# Esquematico.net
KiCad netlist of a schematic drawn in EAGLE
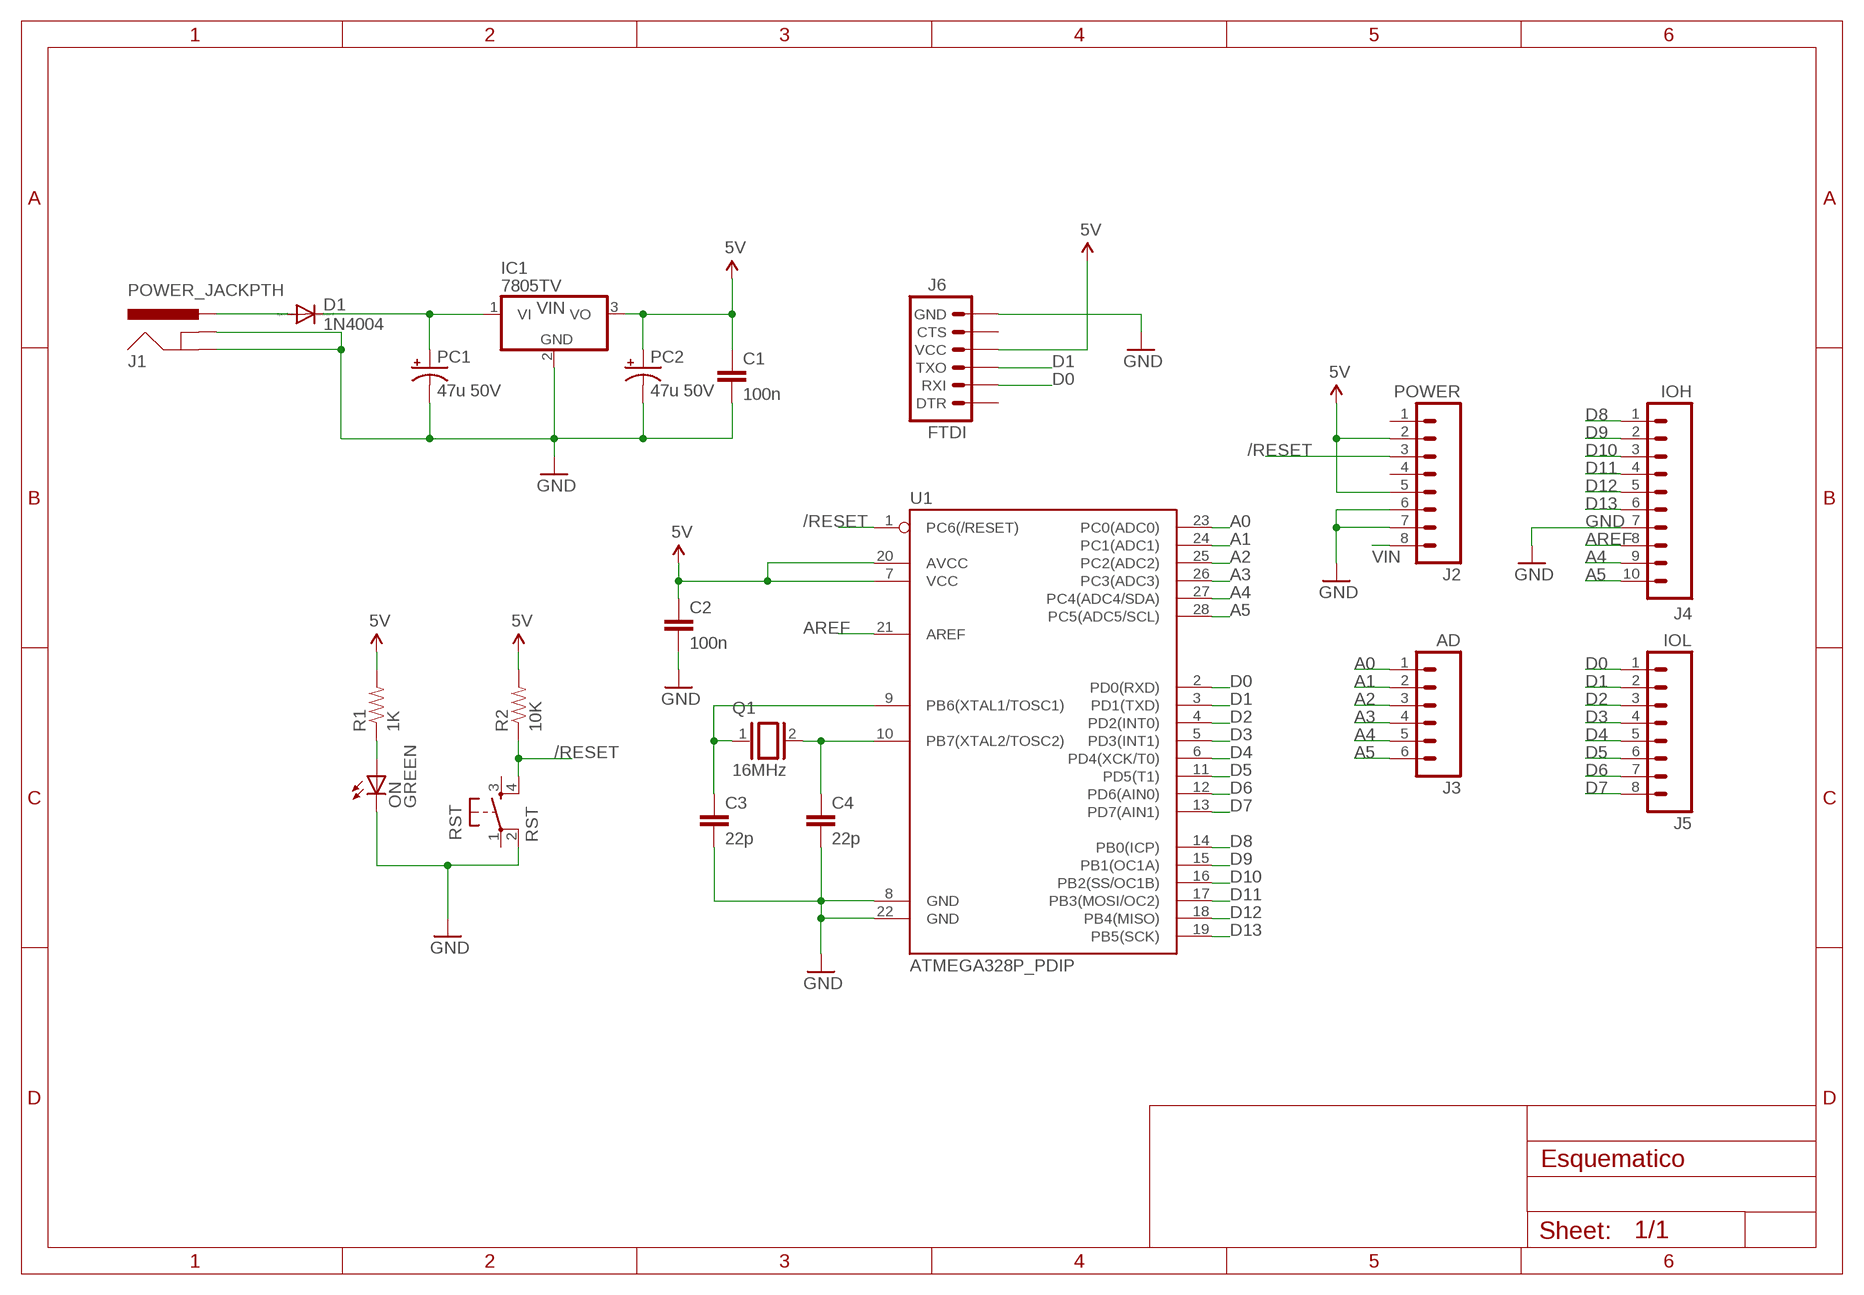
[diagram p0: schematic, sheet 1]

(export (version "E")
  (design (tool "Eeschema 10.0.6"))
  (components
    (comp (ref "C1")
      (value "100n")
      (footprint "eagle-import:C2.5-3")
      (libsource (lib "eagle-import") (part "C2,5-3"))
    )
    (comp (ref "C2")
      (value "100n")
      (footprint "eagle-import:CAP-PTH-SMALLEZ")
      (libsource (lib "eagle-import") (part "CAPEZ"))
    )
    (comp (ref "C3")
      (value "22p")
      (footprint "eagle-import:CAP-PTH-SMALLEZ")
      (libsource (lib "eagle-import") (part "CAPEZ"))
    )
    (comp (ref "C4")
      (value "22p")
      (footprint "eagle-import:CAP-PTH-SMALLEZ")
      (libsource (lib "eagle-import") (part "CAPEZ"))
    )
    (comp (ref "D1")
      (value "1N4004")
      (footprint "eagle-import:DO41-10")
      (libsource (lib "eagle-import") (part "1N4004"))
    )
    (comp (ref "IC1")
      (value "7805TV")
      (footprint "eagle-import:TO220V")
      (libsource (lib "eagle-import") (part "78TV05"))
    )
    (comp (ref "J1")
      (value "POWER_JACKPTH")
      (footprint "eagle-import:POWER_JACK_PTH")
      (libsource (lib "eagle-import") (part "POWER_JACKPTH"))
    )
    (comp (ref "J2")
      (value "POWER")
      (footprint "eagle-import:1X08_PIN1_NO_SILK")
      (libsource (lib "eagle-import") (part "M08NO_SILK"))
    )
    (comp (ref "J3")
      (value "AD")
      (footprint "eagle-import:1X06_NO_SILK")
      (libsource (lib "eagle-import") (part "M06NO_SILK_FEMALE_PTH"))
    )
    (comp (ref "J4")
      (value "IOH")
      (footprint "eagle-import:1X10_NO_SILK")
      (libsource (lib "eagle-import") (part "M10NO_SILK_PTH_FEMALE"))
    )
    (comp (ref "J5")
      (value "IOL")
      (footprint "eagle-import:1X08_PIN1_NO_SILK")
      (libsource (lib "eagle-import") (part "M08NO_SILK"))
    )
    (comp (ref "J6")
      (value "FTDI")
      (footprint "eagle-import:1X06")
      (libsource (lib "eagle-import") (part "ARDUINO_SERIAL_PROGRAMPTH"))
    )
    (comp (ref "ON")
      (value "GREEN")
      (footprint "eagle-import:LED3MM")
      (libsource (lib "eagle-import") (part "LED3MM"))
    )
    (comp (ref "PC1")
      (value "47u 50V")
      (footprint "eagle-import:TAP5-50")
      (libsource (lib "eagle-import") (part "CPOL-USTAP5-50"))
    )
    (comp (ref "PC2")
      (value "47u 50V")
      (footprint "eagle-import:TAP5-50")
      (libsource (lib "eagle-import") (part "CPOL-USTAP5-50"))
    )
    (comp (ref "Q1")
      (value "16MHz")
      (footprint "eagle-import:QS")
      (libsource (lib "eagle-import") (part "XTAL/S"))
    )
    (comp (ref "R1")
      (value "1K")
      (footprint "eagle-import:AXIAL-0.3")
      (libsource (lib "eagle-import") (part "1KOHM-1/4W-1%(PTH)"))
    )
    (comp (ref "R2")
      (value "10K")
      (footprint "eagle-import:AXIAL-0.3")
      (libsource (lib "eagle-import") (part "1KOHM-1/4W-1%(PTH)"))
    )
    (comp (ref "RST")
      (value "RST")
      (footprint "eagle-import:TAC-SWITCH-PTH")
      (libsource (lib "eagle-import") (part "TACTILE-SWITCH-PTH"))
    )
    (comp (ref "U1")
      (value "ATMEGA328P_PDIP")
      (footprint "eagle-import:DIL28-3")
      (libsource (lib "eagle-import") (part "ATMEGA328P_PDIP"))
    )
  )
  (nets
    (net (code "1") (name "/A0") (class "Default")
      (node (ref "J3") (pin "1") (pinfunction "1_1") (pintype "passive"))
      (node (ref "U1") (pin "23") (pinfunction "PC0(ADC0)_23") (pintype "bidirectional"))
    )
    (net (code "2") (name "/A1") (class "Default")
      (node (ref "J3") (pin "2") (pinfunction "2_2") (pintype "passive"))
      (node (ref "U1") (pin "24") (pinfunction "PC1(ADC1)_24") (pintype "bidirectional"))
    )
    (net (code "3") (name "/A2") (class "Default")
      (node (ref "J3") (pin "3") (pinfunction "3_3") (pintype "passive"))
      (node (ref "U1") (pin "25") (pinfunction "PC2(ADC2)_25") (pintype "bidirectional"))
    )
    (net (code "4") (name "/A3") (class "Default")
      (node (ref "J3") (pin "4") (pinfunction "4_4") (pintype "passive"))
      (node (ref "U1") (pin "26") (pinfunction "PC3(ADC3)_26") (pintype "bidirectional"))
    )
    (net (code "5") (name "/A4") (class "Default")
      (node (ref "J3") (pin "5") (pinfunction "5_5") (pintype "passive"))
      (node (ref "J4") (pin "9") (pinfunction "9_9") (pintype "passive"))
      (node (ref "U1") (pin "27") (pinfunction "PC4(ADC4/SDA)_27") (pintype "bidirectional"))
    )
    (net (code "6") (name "/A5") (class "Default")
      (node (ref "J3") (pin "6") (pinfunction "6_6") (pintype "passive"))
      (node (ref "J4") (pin "10") (pinfunction "10_10") (pintype "passive"))
      (node (ref "U1") (pin "28") (pinfunction "PC5(ADC5/SCL)_28") (pintype "bidirectional"))
    )
    (net (code "7") (name "/AREF") (class "Default")
      (node (ref "J4") (pin "8") (pinfunction "8_8") (pintype "passive"))
      (node (ref "U1") (pin "21") (pinfunction "AREF_21") (pintype "bidirectional"))
    )
    (net (code "8") (name "/D0") (class "Default")
      (node (ref "J5") (pin "1") (pinfunction "1_1") (pintype "passive"))
      (node (ref "J6") (pin "2") (pinfunction "RXI_2") (pintype "passive"))
      (node (ref "U1") (pin "2") (pinfunction "PD0(RXD)_2") (pintype "bidirectional"))
    )
    (net (code "9") (name "/D1") (class "Default")
      (node (ref "J5") (pin "2") (pinfunction "2_2") (pintype "passive"))
      (node (ref "J6") (pin "3") (pinfunction "TXO_3") (pintype "passive"))
      (node (ref "U1") (pin "3") (pinfunction "PD1(TXD)_3") (pintype "bidirectional"))
    )
    (net (code "10") (name "/D2") (class "Default")
      (node (ref "J5") (pin "3") (pinfunction "3_3") (pintype "passive"))
      (node (ref "U1") (pin "4") (pinfunction "PD2(INT0)_4") (pintype "bidirectional"))
    )
    (net (code "11") (name "/D3") (class "Default")
      (node (ref "J5") (pin "4") (pinfunction "4_4") (pintype "passive"))
      (node (ref "U1") (pin "5") (pinfunction "PD3(INT1)_5") (pintype "bidirectional"))
    )
    (net (code "12") (name "/D4") (class "Default")
      (node (ref "J5") (pin "5") (pinfunction "5_5") (pintype "passive"))
      (node (ref "U1") (pin "6") (pinfunction "PD4(XCK/T0)_6") (pintype "bidirectional"))
    )
    (net (code "13") (name "/D5") (class "Default")
      (node (ref "J5") (pin "6") (pinfunction "6_6") (pintype "passive"))
      (node (ref "U1") (pin "11") (pinfunction "PD5(T1)_11") (pintype "bidirectional"))
    )
    (net (code "14") (name "/D6") (class "Default")
      (node (ref "J5") (pin "7") (pinfunction "7_7") (pintype "passive"))
      (node (ref "U1") (pin "12") (pinfunction "PD6(AIN0)_12") (pintype "bidirectional"))
    )
    (net (code "15") (name "/D7") (class "Default")
      (node (ref "J5") (pin "8") (pinfunction "8_8") (pintype "passive"))
      (node (ref "U1") (pin "13") (pinfunction "PD7(AIN1)_13") (pintype "bidirectional"))
    )
    (net (code "16") (name "/D8") (class "Default")
      (node (ref "J4") (pin "1") (pinfunction "1_1") (pintype "passive"))
      (node (ref "U1") (pin "14") (pinfunction "PB0(ICP)_14") (pintype "bidirectional"))
    )
    (net (code "17") (name "/D9") (class "Default")
      (node (ref "J4") (pin "2") (pinfunction "2_2") (pintype "passive"))
      (node (ref "U1") (pin "15") (pinfunction "PB1(OC1A)_15") (pintype "bidirectional"))
    )
    (net (code "18") (name "/D10") (class "Default")
      (node (ref "J4") (pin "3") (pinfunction "3_3") (pintype "passive"))
      (node (ref "U1") (pin "16") (pinfunction "PB2(SS/OC1B)_16") (pintype "bidirectional"))
    )
    (net (code "19") (name "/D11") (class "Default")
      (node (ref "J4") (pin "4") (pinfunction "4_4") (pintype "passive"))
      (node (ref "U1") (pin "17") (pinfunction "PB3(MOSI/OC2)_17") (pintype "bidirectional"))
    )
    (net (code "20") (name "/D12") (class "Default")
      (node (ref "J4") (pin "5") (pinfunction "5_5") (pintype "passive"))
      (node (ref "U1") (pin "18") (pinfunction "PB4(MISO)_18") (pintype "bidirectional"))
    )
    (net (code "21") (name "/D13") (class "Default")
      (node (ref "J4") (pin "6") (pinfunction "6_6") (pintype "passive"))
      (node (ref "U1") (pin "19") (pinfunction "PB5(SCK)_19") (pintype "bidirectional"))
    )
    (net (code "22") (name "/VIN") (class "Default")
      (node (ref "D1") (pin "C") (pinfunction "C_C") (pintype "passive"))
      (node (ref "IC1") (pin "1") (pinfunction "VI_1") (pintype "input"))
      (node (ref "J2") (pin "8") (pinfunction "8_8") (pintype "passive"))
      (node (ref "PC1") (pin "+") (pinfunction "+_+") (pintype "passive"))
    )
    (net (code "23") (name "/{slash}RESET") (class "Default")
      (node (ref "J2") (pin "3") (pinfunction "3_3") (pintype "passive"))
      (node (ref "R2") (pin "P$1") (pinfunction "1_P$1") (pintype "passive"))
      (node (ref "RST") (pin "4") (pinfunction "4_4") (pintype "passive"))
      (node (ref "U1") (pin "1") (pinfunction "PC6(/RESET)_1") (pintype "bidirectional"))
    )
    (net (code "24") (name "5V") (class "Default")
      (node (ref "C1") (pin "1") (pinfunction "1_1") (pintype "passive"))
      (node (ref "C2") (pin "1") (pinfunction "1_1") (pintype "passive"))
      (node (ref "IC1") (pin "3") (pinfunction "VO_3") (pintype "passive"))
      (node (ref "J2") (pin "2") (pinfunction "2_2") (pintype "passive"))
      (node (ref "J2") (pin "5") (pinfunction "5_5") (pintype "passive"))
      (node (ref "J6") (pin "4") (pinfunction "VCC_4") (pintype "passive"))
      (node (ref "PC2") (pin "+") (pinfunction "+_+") (pintype "passive"))
      (node (ref "R1") (pin "P$2") (pinfunction "2_P$2") (pintype "passive"))
      (node (ref "R2") (pin "P$2") (pinfunction "2_P$2") (pintype "passive"))
      (node (ref "U1") (pin "20") (pinfunction "AVCC_20") (pintype "bidirectional"))
      (node (ref "U1") (pin "7") (pinfunction "VCC_7") (pintype "bidirectional"))
    )
    (net (code "25") (name "GND") (class "Default")
      (node (ref "C1") (pin "2") (pinfunction "2_2") (pintype "passive"))
      (node (ref "C2") (pin "2") (pinfunction "2_2") (pintype "passive"))
      (node (ref "C3") (pin "2") (pinfunction "2_2") (pintype "passive"))
      (node (ref "C4") (pin "2") (pinfunction "2_2") (pintype "passive"))
      (node (ref "IC1") (pin "2") (pinfunction "GND_2") (pintype "passive"))
      (node (ref "J1") (pin "GND") (pinfunction "GND_GND") (pintype "bidirectional"))
      (node (ref "J1") (pin "GNDBREAK") (pinfunction "GNDBREAK_GNDBREAK") (pintype "bidirectional"))
      (node (ref "J2") (pin "6") (pinfunction "6_6") (pintype "passive"))
      (node (ref "J2") (pin "7") (pinfunction "7_7") (pintype "passive"))
      (node (ref "J4") (pin "7") (pinfunction "7_7") (pintype "passive"))
      (node (ref "J6") (pin "6") (pinfunction "GND_6") (pintype "passive"))
      (node (ref "ON") (pin "K") (pinfunction "C_K") (pintype "passive"))
      (node (ref "PC1") (pin "-") (pinfunction "-_-") (pintype "passive"))
      (node (ref "PC2") (pin "-") (pinfunction "-_-") (pintype "passive"))
      (node (ref "RST") (pin "2") (pinfunction "2_2") (pintype "passive"))
      (node (ref "U1") (pin "22") (pinfunction "GND_22") (pintype "bidirectional"))
      (node (ref "U1") (pin "8") (pinfunction "GND_8") (pintype "bidirectional"))
    )
    (net (code "26") (name "Net-(D1-PadA)") (class "Default")
      (node (ref "D1") (pin "A") (pinfunction "A_A") (pintype "passive"))
      (node (ref "J1") (pin "PWR") (pinfunction "PWR_PWR") (pintype "bidirectional"))
    )
    (net (code "27") (name "Net-(R1-1)") (class "Default")
      (node (ref "ON") (pin "A") (pinfunction "A_A") (pintype "passive"))
      (node (ref "R1") (pin "P$1") (pinfunction "1_P$1") (pintype "passive"))
    )
    (net (code "28") (name "Net-(U1-PB6(XTAL1{slash}TOSC1))") (class "Default")
      (node (ref "C3") (pin "1") (pinfunction "1_1") (pintype "passive"))
      (node (ref "Q1") (pin "1") (pinfunction "1_1") (pintype "passive"))
      (node (ref "U1") (pin "9") (pinfunction "PB6(XTAL1/TOSC1)_9") (pintype "bidirectional"))
    )
    (net (code "29") (name "Net-(U1-PB7(XTAL2{slash}TOSC2))") (class "Default")
      (node (ref "C4") (pin "1") (pinfunction "1_1") (pintype "passive"))
      (node (ref "Q1") (pin "2") (pinfunction "2_2") (pintype "passive"))
      (node (ref "U1") (pin "10") (pinfunction "PB7(XTAL2/TOSC2)_10") (pintype "bidirectional"))
    )
    (net (code "30") (name "unconnected-(J2-Pad1)") (class "Default")
      (node (ref "J2") (pin "1") (pinfunction "1_1") (pintype "passive"))
    )
    (net (code "31") (name "unconnected-(J2-Pad4)") (class "Default")
      (node (ref "J2") (pin "4") (pinfunction "4_4") (pintype "passive"))
    )
    (net (code "32") (name "unconnected-(J6-CTS-Pad5)") (class "Default")
      (node (ref "J6") (pin "5") (pinfunction "CTS_5") (pintype "passive"))
    )
    (net (code "33") (name "unconnected-(J6-DTR-Pad1)") (class "Default")
      (node (ref "J6") (pin "1") (pinfunction "DTR_1") (pintype "passive"))
    )
    (net (code "34") (name "unconnected-(RST-Pad1)") (class "Default")
      (node (ref "RST") (pin "1") (pinfunction "1_1") (pintype "passive"))
    )
    (net (code "35") (name "unconnected-(RST-Pad3)") (class "Default")
      (node (ref "RST") (pin "3") (pinfunction "3_3") (pintype "passive"))
    )
  )
)
